# Sheet1.net
KiCad netlist of a schematic drawn in Altium Designer
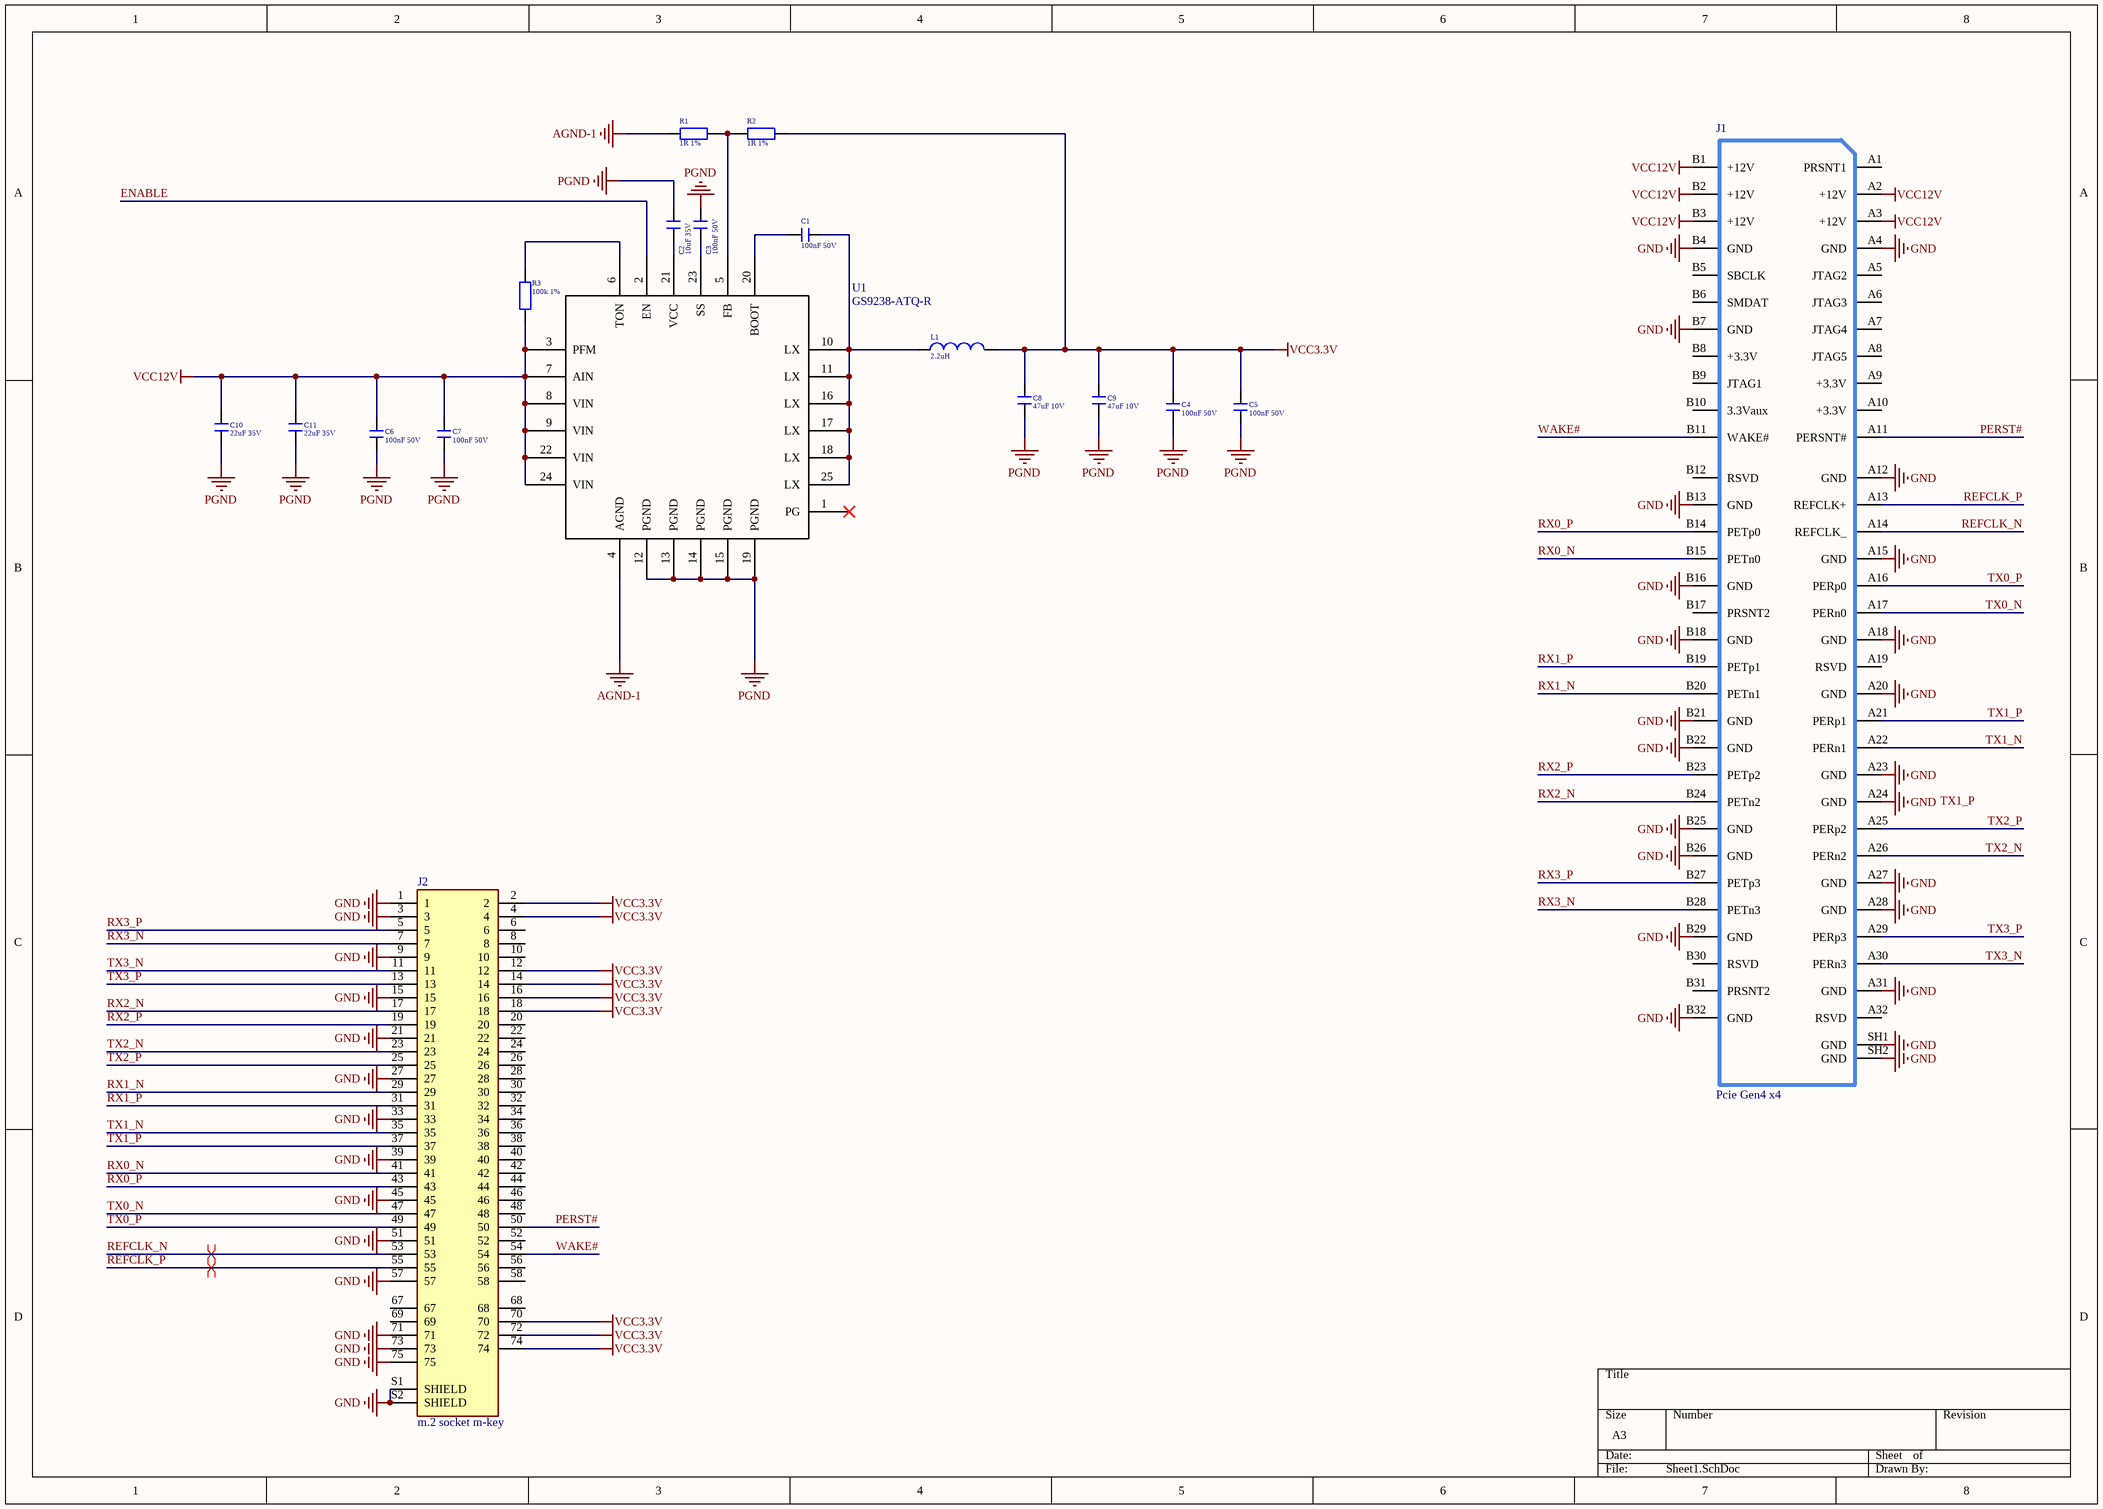
[diagram p0: Sheet1.SchDoc]

(export (version "E")
  (design (tool "Eeschema 10.0.6"))
  (components
    (comp (ref "C1")
      (value "100nF 50V")
      (footprint "C0603_l")
      (description "无极性贴片电容")
      (fields (field (name "版权归属") "源创客"))
      (libsource (lib "Capacitor") (part "C"))
    )
    (comp (ref "C2")
      (value "10uF 35V")
      (footprint "C0603_l")
      (description "无极性贴片电容")
      (fields (field (name "版权归属") "源创客"))
      (libsource (lib "Capacitor") (part "C"))
    )
    (comp (ref "C3")
      (value "100nF 50V")
      (footprint "C0603_l")
      (description "无极性贴片电容")
      (fields (field (name "版权归属") "源创客"))
      (libsource (lib "Capacitor") (part "C"))
    )
    (comp (ref "C4")
      (value "100nF 50V")
      (footprint "C0603_l")
      (description "无极性贴片电容")
      (fields (field (name "版权归属") "源创客"))
      (libsource (lib "Capacitor") (part "C"))
    )
    (comp (ref "C5")
      (value "100nF 50V")
      (footprint "C0603_l")
      (description "无极性贴片电容")
      (fields (field (name "版权归属") "源创客"))
      (libsource (lib "Capacitor") (part "C"))
    )
    (comp (ref "C6")
      (value "100nF 50V")
      (footprint "C0603_l")
      (description "无极性贴片电容")
      (fields (field (name "版权归属") "源创客"))
      (libsource (lib "Capacitor") (part "C"))
    )
    (comp (ref "C7")
      (value "100nF 50V")
      (footprint "C0603_l")
      (description "无极性贴片电容")
      (fields (field (name "版权归属") "源创客"))
      (libsource (lib "Capacitor") (part "C"))
    )
    (comp (ref "C8")
      (value "47uF 10V")
      (footprint "C1206_l")
      (description "无极性贴片电容")
      (fields (field (name "版权归属") "源创客"))
      (libsource (lib "Capacitor") (part "C"))
    )
    (comp (ref "C9")
      (value "47uF 10V")
      (footprint "C1206_l")
      (description "无极性贴片电容")
      (fields (field (name "版权归属") "源创客"))
      (libsource (lib "Capacitor") (part "C"))
    )
    (comp (ref "C10")
      (value "22uF 35V")
      (footprint "C1206_l")
      (description "无极性贴片电容")
      (fields (field (name "版权归属") "源创客"))
      (libsource (lib "Capacitor") (part "C"))
    )
    (comp (ref "C11")
      (value "22uF 35V")
      (footprint "C1206_l")
      (description "无极性贴片电容")
      (fields (field (name "版权归属") "源创客"))
      (libsource (lib "Capacitor") (part "C"))
    )
    (comp (ref "J1")
      (value "Pcie Gen4 x4")
      (footprint "PCIEDGE_X4-A")
      (libsource (lib "Connector-PCIE") (part "Pcie Gen4 x4"))
    )
    (comp (ref "J2")
      (value "m.2 socket m-key")
      (footprint "M.2接口 4.2H")
      (description "M.2接口")
      (fields (field (name "MF") "Amphenol ICC (FCI)") (field (name "MP") "MDT420M01002"))
      (libsource (lib "Connector-PCIE") (part "M.2接口"))
    )
    (comp (ref "L1")
      (value "2.2uH")
      (footprint "NR6028")
      (description "小功率贴片电感")
      (fields (field (name "版权归属") "源创客"))
      (libsource (lib "Inductor") (part "L"))
    )
    (comp (ref "R1")
      (value "1R 1%")
      (footprint "R 0603_L")
      (description "贴片电阻")
      (fields (field (name "版权归属") "源创客"))
      (libsource (lib "Resistor") (part "R"))
    )
    (comp (ref "R2")
      (value "1R 1%")
      (footprint "R 0603_L")
      (description "贴片电阻")
      (fields (field (name "版权归属") "源创客"))
      (libsource (lib "Resistor") (part "R"))
    )
    (comp (ref "R3")
      (value "100k 1%")
      (footprint "R 0603_L")
      (description "贴片电阻")
      (fields (field (name "版权归属") "源创客"))
      (libsource (lib "Resistor") (part "R"))
    )
    (comp (ref "U1")
      (value "GS9238-ATQ-R")
      (footprint "TQFN-23_L4.0-W4.0-P0.50-BL_GS9238TQ-R")
      (description "DCDC降压芯片")
      (libsource (lib "DCDC Convert") (part "GS9238-ATQ-R"))
    )
  )
  (nets
    (net (code "1") (name "/ENABLE") (class "Default")
      (node (ref "U1") (pin "2") (pinfunction "EN_2") (pintype "passive"))
    )
    (net (code "2") (name "/PERST#") (class "Default")
      (node (ref "J1") (pin "A11") (pinfunction "PERSNT#_A11") (pintype "passive"))
      (node (ref "J2") (pin "50") (pinfunction "50_50") (pintype "passive"))
    )
    (net (code "3") (name "/REFCLK_N") (class "Default")
      (node (ref "J1") (pin "A14") (pinfunction "REFCLK__A14") (pintype "passive"))
      (node (ref "J2") (pin "53") (pinfunction "53_53") (pintype "passive"))
    )
    (net (code "4") (name "/REFCLK_P") (class "Default")
      (node (ref "J1") (pin "A13") (pinfunction "REFCLK+_A13") (pintype "passive"))
      (node (ref "J2") (pin "55") (pinfunction "55_55") (pintype "passive"))
    )
    (net (code "5") (name "/RX0_N") (class "Default")
      (node (ref "J1") (pin "B15") (pinfunction "PETn0_B15") (pintype "passive"))
      (node (ref "J2") (pin "41") (pinfunction "41_41") (pintype "passive"))
    )
    (net (code "6") (name "/RX0_P") (class "Default")
      (node (ref "J1") (pin "B14") (pinfunction "PETp0_B14") (pintype "passive"))
      (node (ref "J2") (pin "43") (pinfunction "43_43") (pintype "passive"))
    )
    (net (code "7") (name "/RX1_N") (class "Default")
      (node (ref "J1") (pin "B20") (pinfunction "PETn1_B20") (pintype "passive"))
      (node (ref "J2") (pin "29") (pinfunction "29_29") (pintype "passive"))
    )
    (net (code "8") (name "/RX1_P") (class "Default")
      (node (ref "J1") (pin "B19") (pinfunction "PETp1_B19") (pintype "passive"))
      (node (ref "J2") (pin "31") (pinfunction "31_31") (pintype "passive"))
    )
    (net (code "9") (name "/RX2_N") (class "Default")
      (node (ref "J1") (pin "B24") (pinfunction "PETn2_B24") (pintype "passive"))
      (node (ref "J2") (pin "17") (pinfunction "17_17") (pintype "passive"))
    )
    (net (code "10") (name "/RX2_P") (class "Default")
      (node (ref "J1") (pin "B23") (pinfunction "PETp2_B23") (pintype "passive"))
      (node (ref "J2") (pin "19") (pinfunction "19_19") (pintype "passive"))
    )
    (net (code "11") (name "/RX3_N") (class "Default")
      (node (ref "J1") (pin "B28") (pinfunction "PETn3_B28") (pintype "passive"))
      (node (ref "J2") (pin "7") (pinfunction "7_7") (pintype "passive"))
    )
    (net (code "12") (name "/RX3_P") (class "Default")
      (node (ref "J1") (pin "B27") (pinfunction "PETp3_B27") (pintype "passive"))
      (node (ref "J2") (pin "5") (pinfunction "5_5") (pintype "passive"))
    )
    (net (code "13") (name "/TX0_N") (class "Default")
      (node (ref "J1") (pin "A17") (pinfunction "PERn0_A17") (pintype "passive"))
      (node (ref "J2") (pin "47") (pinfunction "47_47") (pintype "passive"))
    )
    (net (code "14") (name "/TX0_P") (class "Default")
      (node (ref "J1") (pin "A16") (pinfunction "PERp0_A16") (pintype "passive"))
      (node (ref "J2") (pin "49") (pinfunction "49_49") (pintype "passive"))
    )
    (net (code "15") (name "/TX1_N") (class "Default")
      (node (ref "J1") (pin "A22") (pinfunction "PERn1_A22") (pintype "passive"))
      (node (ref "J2") (pin "35") (pinfunction "35_35") (pintype "passive"))
    )
    (net (code "16") (name "/TX1_P") (class "Default")
      (node (ref "J1") (pin "A21") (pinfunction "PERp1_A21") (pintype "passive"))
      (node (ref "J2") (pin "37") (pinfunction "37_37") (pintype "passive"))
    )
    (net (code "17") (name "/TX2_N") (class "Default")
      (node (ref "J1") (pin "A26") (pinfunction "PERn2_A26") (pintype "passive"))
      (node (ref "J2") (pin "23") (pinfunction "23_23") (pintype "passive"))
    )
    (net (code "18") (name "/TX2_P") (class "Default")
      (node (ref "J1") (pin "A25") (pinfunction "PERp2_A25") (pintype "passive"))
      (node (ref "J2") (pin "25") (pinfunction "25_25") (pintype "passive"))
    )
    (net (code "19") (name "/TX3_N") (class "Default")
      (node (ref "J1") (pin "A30") (pinfunction "PERn3_A30") (pintype "passive"))
      (node (ref "J2") (pin "11") (pinfunction "11_11") (pintype "passive"))
    )
    (net (code "20") (name "/TX3_P") (class "Default")
      (node (ref "J1") (pin "A29") (pinfunction "PERp3_A29") (pintype "passive"))
      (node (ref "J2") (pin "13") (pinfunction "13_13") (pintype "passive"))
    )
    (net (code "21") (name "/WAKE#") (class "Default")
      (node (ref "J1") (pin "B11") (pinfunction "WAKE#_B11") (pintype "passive"))
      (node (ref "J2") (pin "54") (pinfunction "54_54") (pintype "passive"))
    )
    (net (code "22") (name "AGND-1") (class "Default")
      (node (ref "R1") (pin "1") (pinfunction "1_1") (pintype "passive"))
      (node (ref "U1") (pin "4") (pinfunction "AGND_4") (pintype "passive"))
    )
    (net (code "23") (name "GND") (class "Default")
      (node (ref "J1") (pin "A12") (pinfunction "GND_A12") (pintype "passive"))
      (node (ref "J1") (pin "A15") (pinfunction "GND_A15") (pintype "passive"))
      (node (ref "J1") (pin "A18") (pinfunction "GND_A18") (pintype "passive"))
      (node (ref "J1") (pin "A20") (pinfunction "GND_A20") (pintype "passive"))
      (node (ref "J1") (pin "A23") (pinfunction "GND_A23") (pintype "passive"))
      (node (ref "J1") (pin "A24") (pinfunction "GND_A24") (pintype "passive"))
      (node (ref "J1") (pin "A27") (pinfunction "GND_A27") (pintype "passive"))
      (node (ref "J1") (pin "A28") (pinfunction "GND_A28") (pintype "passive"))
      (node (ref "J1") (pin "A31") (pinfunction "GND_A31") (pintype "passive"))
      (node (ref "J1") (pin "A4") (pinfunction "GND_A4") (pintype "passive"))
      (node (ref "J1") (pin "B13") (pinfunction "GND_B13") (pintype "passive"))
      (node (ref "J1") (pin "B16") (pinfunction "GND_B16") (pintype "passive"))
      (node (ref "J1") (pin "B18") (pinfunction "GND_B18") (pintype "passive"))
      (node (ref "J1") (pin "B21") (pinfunction "GND_B21") (pintype "passive"))
      (node (ref "J1") (pin "B22") (pinfunction "GND_B22") (pintype "passive"))
      (node (ref "J1") (pin "B25") (pinfunction "GND_B25") (pintype "passive"))
      (node (ref "J1") (pin "B26") (pinfunction "GND_B26") (pintype "passive"))
      (node (ref "J1") (pin "B29") (pinfunction "GND_B29") (pintype "passive"))
      (node (ref "J1") (pin "B32") (pinfunction "GND_B32") (pintype "passive"))
      (node (ref "J1") (pin "B4") (pinfunction "GND_B4") (pintype "passive"))
      (node (ref "J1") (pin "B7") (pinfunction "GND_B7") (pintype "passive"))
      (node (ref "J1") (pin "SH1") (pinfunction "GND_SH1") (pintype "passive"))
      (node (ref "J1") (pin "SH2") (pinfunction "GND_SH2") (pintype "passive"))
      (node (ref "J2") (pin "1") (pinfunction "1_1") (pintype "passive"))
      (node (ref "J2") (pin "15") (pinfunction "15_15") (pintype "power_in"))
      (node (ref "J2") (pin "21") (pinfunction "21_21") (pintype "power_in"))
      (node (ref "J2") (pin "27") (pinfunction "27_27") (pintype "power_in"))
      (node (ref "J2") (pin "3") (pinfunction "3_3") (pintype "power_in"))
      (node (ref "J2") (pin "33") (pinfunction "33_33") (pintype "power_in"))
      (node (ref "J2") (pin "39") (pinfunction "39_39") (pintype "power_in"))
      (node (ref "J2") (pin "45") (pinfunction "45_45") (pintype "power_in"))
      (node (ref "J2") (pin "51") (pinfunction "51_51") (pintype "power_in"))
      (node (ref "J2") (pin "57") (pinfunction "57_57") (pintype "power_in"))
      (node (ref "J2") (pin "71") (pinfunction "71_71") (pintype "passive"))
      (node (ref "J2") (pin "73") (pinfunction "73_73") (pintype "passive"))
      (node (ref "J2") (pin "75") (pinfunction "75_75") (pintype "passive"))
      (node (ref "J2") (pin "9") (pinfunction "9_9") (pintype "power_in"))
      (node (ref "J2") (pin "S1") (pinfunction "SHIELD_S1") (pintype "passive"))
      (node (ref "J2") (pin "S2") (pinfunction "SHIELD_S2") (pintype "passive"))
    )
    (net (code "24") (name "Net-(C1-Pad1)") (class "Default")
      (node (ref "C1") (pin "1") (pinfunction "1_1") (pintype "passive"))
      (node (ref "L1") (pin "2") (pinfunction "2_2") (pintype "passive"))
      (node (ref "U1") (pin "10") (pinfunction "LX_10") (pintype "passive"))
      (node (ref "U1") (pin "11") (pinfunction "LX_11") (pintype "passive"))
      (node (ref "U1") (pin "16") (pinfunction "LX_16") (pintype "passive"))
      (node (ref "U1") (pin "17") (pinfunction "LX_17") (pintype "passive"))
      (node (ref "U1") (pin "18") (pinfunction "LX_18") (pintype "passive"))
      (node (ref "U1") (pin "25") (pinfunction "LX_25") (pintype "passive"))
    )
    (net (code "25") (name "Net-(U1-BOOT)") (class "Default")
      (node (ref "C1") (pin "2") (pinfunction "2_2") (pintype "passive"))
      (node (ref "U1") (pin "20") (pinfunction "BOOT_20") (pintype "passive"))
    )
    (net (code "26") (name "Net-(U1-FB)") (class "Default")
      (node (ref "R1") (pin "2") (pinfunction "2_2") (pintype "passive"))
      (node (ref "R2") (pin "1") (pinfunction "1_1") (pintype "passive"))
      (node (ref "U1") (pin "5") (pinfunction "FB_5") (pintype "passive"))
    )
    (net (code "27") (name "Net-(U1-SS)") (class "Default")
      (node (ref "C3") (pin "1") (pinfunction "1_1") (pintype "passive"))
      (node (ref "U1") (pin "23") (pinfunction "SS_23") (pintype "passive"))
    )
    (net (code "28") (name "Net-(U1-TON)") (class "Default")
      (node (ref "R3") (pin "2") (pinfunction "2_2") (pintype "passive"))
      (node (ref "U1") (pin "6") (pinfunction "TON_6") (pintype "passive"))
    )
    (net (code "29") (name "Net-(U1-VCC)") (class "Default")
      (node (ref "C2") (pin "1") (pinfunction "1_1") (pintype "passive"))
      (node (ref "U1") (pin "21") (pinfunction "VCC_21") (pintype "passive"))
    )
    (net (code "30") (name "PGND") (class "Default")
      (node (ref "C10") (pin "1") (pinfunction "1_1") (pintype "passive"))
      (node (ref "C11") (pin "1") (pinfunction "1_1") (pintype "passive"))
      (node (ref "C2") (pin "2") (pinfunction "2_2") (pintype "passive"))
      (node (ref "C3") (pin "2") (pinfunction "2_2") (pintype "passive"))
      (node (ref "C4") (pin "1") (pinfunction "1_1") (pintype "passive"))
      (node (ref "C5") (pin "1") (pinfunction "1_1") (pintype "passive"))
      (node (ref "C6") (pin "1") (pinfunction "1_1") (pintype "passive"))
      (node (ref "C7") (pin "1") (pinfunction "1_1") (pintype "passive"))
      (node (ref "C8") (pin "1") (pinfunction "1_1") (pintype "passive"))
      (node (ref "C9") (pin "1") (pinfunction "1_1") (pintype "passive"))
      (node (ref "U1") (pin "12") (pinfunction "PGND_12") (pintype "passive"))
      (node (ref "U1") (pin "13") (pinfunction "PGND_13") (pintype "passive"))
      (node (ref "U1") (pin "14") (pinfunction "PGND_14") (pintype "passive"))
      (node (ref "U1") (pin "15") (pinfunction "PGND_15") (pintype "passive"))
      (node (ref "U1") (pin "19") (pinfunction "PGND_19") (pintype "passive"))
    )
    (net (code "31") (name "VCC3.3V") (class "Default")
      (node (ref "C4") (pin "2") (pinfunction "2_2") (pintype "passive"))
      (node (ref "C5") (pin "2") (pinfunction "2_2") (pintype "passive"))
      (node (ref "C8") (pin "2") (pinfunction "2_2") (pintype "passive"))
      (node (ref "C9") (pin "2") (pinfunction "2_2") (pintype "passive"))
      (node (ref "J2") (pin "12") (pinfunction "12_12") (pintype "passive"))
      (node (ref "J2") (pin "14") (pinfunction "14_14") (pintype "passive"))
      (node (ref "J2") (pin "16") (pinfunction "16_16") (pintype "passive"))
      (node (ref "J2") (pin "18") (pinfunction "18_18") (pintype "passive"))
      (node (ref "J2") (pin "2") (pinfunction "2_2") (pintype "passive"))
      (node (ref "J2") (pin "4") (pinfunction "4_4") (pintype "passive"))
      (node (ref "J2") (pin "70") (pinfunction "70_70") (pintype "passive"))
      (node (ref "J2") (pin "72") (pinfunction "72_72") (pintype "passive"))
      (node (ref "J2") (pin "74") (pinfunction "74_74") (pintype "passive"))
      (node (ref "L1") (pin "1") (pinfunction "1_1") (pintype "passive"))
      (node (ref "R2") (pin "2") (pinfunction "2_2") (pintype "passive"))
    )
    (net (code "32") (name "VCC12V") (class "Default")
      (node (ref "C10") (pin "2") (pinfunction "2_2") (pintype "passive"))
      (node (ref "C11") (pin "2") (pinfunction "2_2") (pintype "passive"))
      (node (ref "C6") (pin "2") (pinfunction "2_2") (pintype "passive"))
      (node (ref "C7") (pin "2") (pinfunction "2_2") (pintype "passive"))
      (node (ref "J1") (pin "A2") (pinfunction "+12V_A2") (pintype "passive"))
      (node (ref "J1") (pin "A3") (pinfunction "+12V_A3") (pintype "passive"))
      (node (ref "J1") (pin "B1") (pinfunction "+12V_B1") (pintype "passive"))
      (node (ref "J1") (pin "B2") (pinfunction "+12V_B2") (pintype "passive"))
      (node (ref "J1") (pin "B3") (pinfunction "+12V_B3") (pintype "passive"))
      (node (ref "R3") (pin "1") (pinfunction "1_1") (pintype "passive"))
      (node (ref "U1") (pin "22") (pinfunction "VIN_22") (pintype "passive"))
      (node (ref "U1") (pin "24") (pinfunction "VIN_24") (pintype "passive"))
      (node (ref "U1") (pin "3") (pinfunction "PFM_3") (pintype "passive"))
      (node (ref "U1") (pin "7") (pinfunction "AIN_7") (pintype "passive"))
      (node (ref "U1") (pin "8") (pinfunction "VIN_8") (pintype "passive"))
      (node (ref "U1") (pin "9") (pinfunction "VIN_9") (pintype "passive"))
    )
    (net (code "33") (name "unconnected-(J1-+3.3V-PadA9)") (class "Default")
      (node (ref "J1") (pin "A9") (pinfunction "+3.3V_A9") (pintype "passive"))
    )
    (net (code "34") (name "unconnected-(J1-+3.3V-PadA10)") (class "Default")
      (node (ref "J1") (pin "A10") (pinfunction "+3.3V_A10") (pintype "passive"))
    )
    (net (code "35") (name "unconnected-(J1-+3.3V-PadB8)") (class "Default")
      (node (ref "J1") (pin "B8") (pinfunction "+3.3V_B8") (pintype "passive"))
    )
    (net (code "36") (name "unconnected-(J1-3.3Vaux-PadB10)") (class "Default")
      (node (ref "J1") (pin "B10") (pinfunction "3.3Vaux_B10") (pintype "passive"))
    )
    (net (code "37") (name "unconnected-(J1-JTAG1-PadB9)") (class "Default")
      (node (ref "J1") (pin "B9") (pinfunction "JTAG1_B9") (pintype "passive"))
    )
    (net (code "38") (name "unconnected-(J1-JTAG2-PadA5)") (class "Default")
      (node (ref "J1") (pin "A5") (pinfunction "JTAG2_A5") (pintype "passive"))
    )
    (net (code "39") (name "unconnected-(J1-JTAG3-PadA6)") (class "Default")
      (node (ref "J1") (pin "A6") (pinfunction "JTAG3_A6") (pintype "passive"))
    )
    (net (code "40") (name "unconnected-(J1-JTAG4-PadA7)") (class "Default")
      (node (ref "J1") (pin "A7") (pinfunction "JTAG4_A7") (pintype "passive"))
    )
    (net (code "41") (name "unconnected-(J1-JTAG5-PadA8)") (class "Default")
      (node (ref "J1") (pin "A8") (pinfunction "JTAG5_A8") (pintype "passive"))
    )
    (net (code "42") (name "unconnected-(J1-PRSNT1-PadA1)") (class "Default")
      (node (ref "J1") (pin "A1") (pinfunction "PRSNT1_A1") (pintype "passive"))
    )
    (net (code "43") (name "unconnected-(J1-PRSNT2-PadB17)") (class "Default")
      (node (ref "J1") (pin "B17") (pinfunction "PRSNT2_B17") (pintype "passive"))
    )
    (net (code "44") (name "unconnected-(J1-PRSNT2-PadB31)") (class "Default")
      (node (ref "J1") (pin "B31") (pinfunction "PRSNT2_B31") (pintype "passive"))
    )
    (net (code "45") (name "unconnected-(J1-RSVD-PadA19)") (class "Default")
      (node (ref "J1") (pin "A19") (pinfunction "RSVD_A19") (pintype "passive"))
    )
    (net (code "46") (name "unconnected-(J1-RSVD-PadA32)") (class "Default")
      (node (ref "J1") (pin "A32") (pinfunction "RSVD_A32") (pintype "passive"))
    )
    (net (code "47") (name "unconnected-(J1-RSVD-PadB12)") (class "Default")
      (node (ref "J1") (pin "B12") (pinfunction "RSVD_B12") (pintype "passive"))
    )
    (net (code "48") (name "unconnected-(J1-RSVD-PadB30)") (class "Default")
      (node (ref "J1") (pin "B30") (pinfunction "RSVD_B30") (pintype "passive"))
    )
    (net (code "49") (name "unconnected-(J1-SBCLK-PadB5)") (class "Default")
      (node (ref "J1") (pin "B5") (pinfunction "SBCLK_B5") (pintype "passive"))
    )
    (net (code "50") (name "unconnected-(J1-SMDAT-PadB6)") (class "Default")
      (node (ref "J1") (pin "B6") (pinfunction "SMDAT_B6") (pintype "passive"))
    )
    (net (code "51") (name "unconnected-(J2-Pad6)") (class "Default")
      (node (ref "J2") (pin "6") (pinfunction "6_6") (pintype "passive"))
    )
    (net (code "52") (name "unconnected-(J2-Pad8)") (class "Default")
      (node (ref "J2") (pin "8") (pinfunction "8_8") (pintype "passive"))
    )
    (net (code "53") (name "unconnected-(J2-Pad10)") (class "Default")
      (node (ref "J2") (pin "10") (pinfunction "10_10") (pintype "passive"))
    )
    (net (code "54") (name "unconnected-(J2-Pad20)") (class "Default")
      (node (ref "J2") (pin "20") (pinfunction "20_20") (pintype "passive"))
    )
    (net (code "55") (name "unconnected-(J2-Pad22)") (class "Default")
      (node (ref "J2") (pin "22") (pinfunction "22_22") (pintype "passive"))
    )
    (net (code "56") (name "unconnected-(J2-Pad24)") (class "Default")
      (node (ref "J2") (pin "24") (pinfunction "24_24") (pintype "passive"))
    )
    (net (code "57") (name "unconnected-(J2-Pad26)") (class "Default")
      (node (ref "J2") (pin "26") (pinfunction "26_26") (pintype "passive"))
    )
    (net (code "58") (name "unconnected-(J2-Pad28)") (class "Default")
      (node (ref "J2") (pin "28") (pinfunction "28_28") (pintype "passive"))
    )
    (net (code "59") (name "unconnected-(J2-Pad30)") (class "Default")
      (node (ref "J2") (pin "30") (pinfunction "30_30") (pintype "passive"))
    )
    (net (code "60") (name "unconnected-(J2-Pad32)") (class "Default")
      (node (ref "J2") (pin "32") (pinfunction "32_32") (pintype "passive"))
    )
    (net (code "61") (name "unconnected-(J2-Pad34)") (class "Default")
      (node (ref "J2") (pin "34") (pinfunction "34_34") (pintype "passive"))
    )
    (net (code "62") (name "unconnected-(J2-Pad36)") (class "Default")
      (node (ref "J2") (pin "36") (pinfunction "36_36") (pintype "passive"))
    )
    (net (code "63") (name "unconnected-(J2-Pad38)") (class "Default")
      (node (ref "J2") (pin "38") (pinfunction "38_38") (pintype "passive"))
    )
    (net (code "64") (name "unconnected-(J2-Pad40)") (class "Default")
      (node (ref "J2") (pin "40") (pinfunction "40_40") (pintype "passive"))
    )
    (net (code "65") (name "unconnected-(J2-Pad42)") (class "Default")
      (node (ref "J2") (pin "42") (pinfunction "42_42") (pintype "passive"))
    )
    (net (code "66") (name "unconnected-(J2-Pad44)") (class "Default")
      (node (ref "J2") (pin "44") (pinfunction "44_44") (pintype "passive"))
    )
    (net (code "67") (name "unconnected-(J2-Pad46)") (class "Default")
      (node (ref "J2") (pin "46") (pinfunction "46_46") (pintype "passive"))
    )
    (net (code "68") (name "unconnected-(J2-Pad48)") (class "Default")
      (node (ref "J2") (pin "48") (pinfunction "48_48") (pintype "passive"))
    )
    (net (code "69") (name "unconnected-(J2-Pad52)") (class "Default")
      (node (ref "J2") (pin "52") (pinfunction "52_52") (pintype "passive"))
    )
    (net (code "70") (name "unconnected-(J2-Pad56)") (class "Default")
      (node (ref "J2") (pin "56") (pinfunction "56_56") (pintype "passive"))
    )
    (net (code "71") (name "unconnected-(J2-Pad58)") (class "Default")
      (node (ref "J2") (pin "58") (pinfunction "58_58") (pintype "passive"))
    )
    (net (code "72") (name "unconnected-(J2-Pad67)") (class "Default")
      (node (ref "J2") (pin "67") (pinfunction "67_67") (pintype "passive"))
    )
    (net (code "73") (name "unconnected-(J2-Pad68)") (class "Default")
      (node (ref "J2") (pin "68") (pinfunction "68_68") (pintype "passive"))
    )
    (net (code "74") (name "unconnected-(J2-Pad69)") (class "Default")
      (node (ref "J2") (pin "69") (pinfunction "69_69") (pintype "passive"))
    )
    (net (code "75") (name "unconnected-(U1-PG-Pad1)") (class "Default")
      (node (ref "U1") (pin "1") (pinfunction "PG_1") (pintype "passive+no_connect"))
    )
  )
)
